# main.net
KiCad netlist of a schematic drawn in Altium Designer
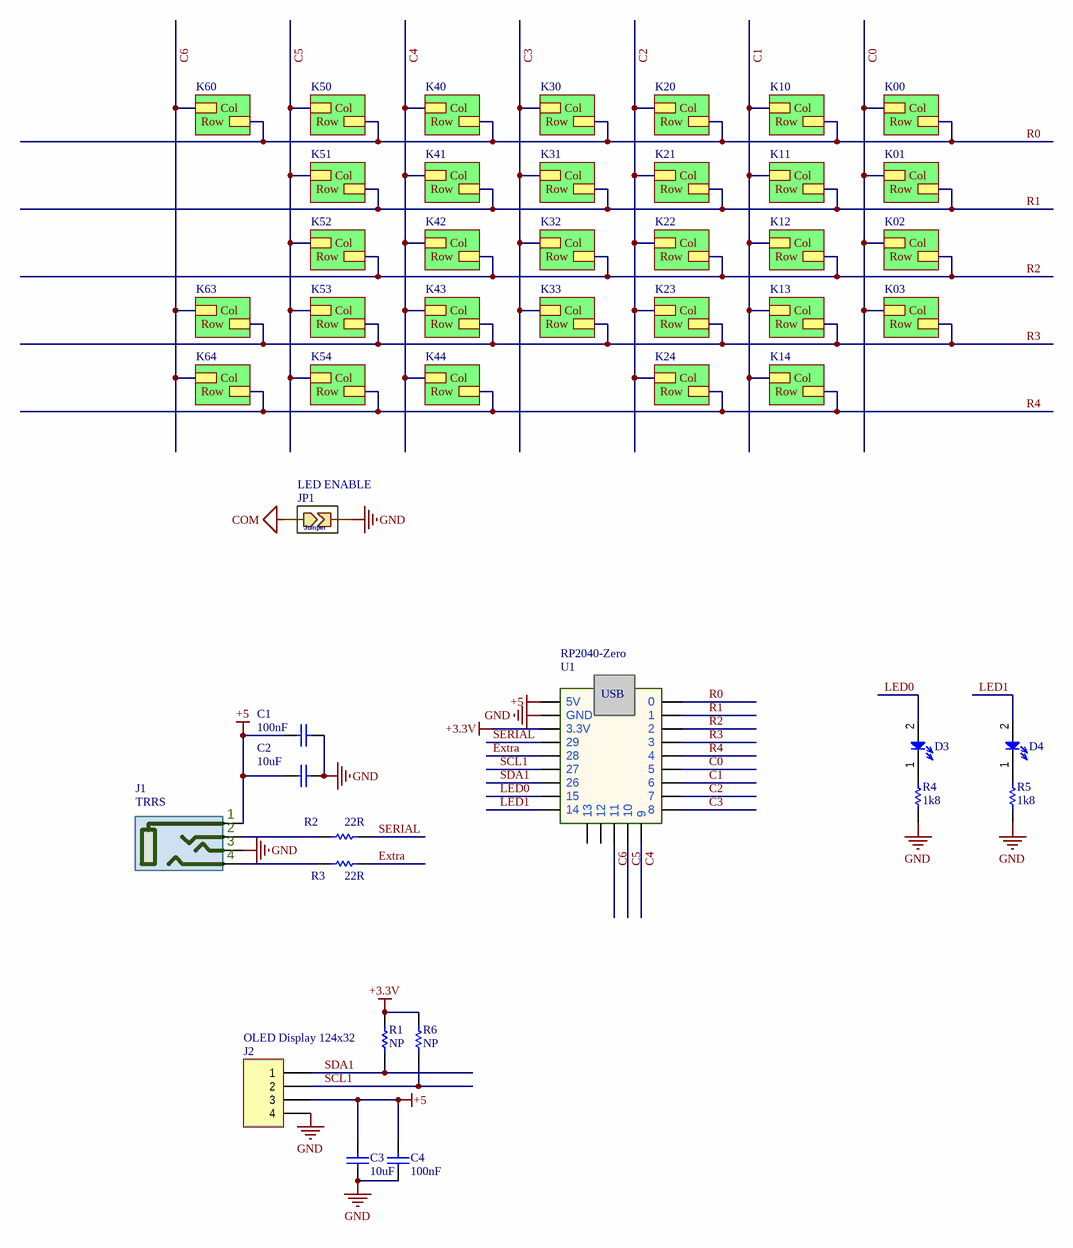
[diagram p0: main.SchDoc]

(export (version "E")
  (design (tool "Eeschema 10.0.6"))
  (components
    (comp (ref "C1")
      (value "100nF")
      (footprint "0402_[1005]")
      (description "Capacitor")
      (libsource (lib "develer_generic") (part "Cap"))
    )
    (comp (ref "C2")
      (value "10uF")
      (footprint "0603_[1608]")
      (description "Capacitor")
      (libsource (lib "develer_generic") (part "Cap"))
    )
    (comp (ref "C3")
      (value "10uF")
      (footprint "0603_[1608]")
      (description "Capacitor")
      (libsource (lib "develer_generic") (part "Cap"))
    )
    (comp (ref "C4")
      (value "100nF")
      (footprint "0402_[1005]")
      (description "Capacitor")
      (libsource (lib "develer_generic") (part "Cap"))
    )
    (comp (ref "D3")
      (value "K")
      (footprint "0402_[1005]_K1-A2_LED")
      (description "Diode Led")
      (fields (field (name "PUBLISHER") "Develer srl"))
      (libsource (lib "develer_generic") (part "DiodeLedSmall"))
    )
    (comp (ref "D4")
      (value "K")
      (footprint "0402_[1005]_K1-A2_LED")
      (description "Diode Led")
      (fields (field (name "PUBLISHER") "Develer srl"))
      (libsource (lib "develer_generic") (part "DiodeLedSmall"))
    )
    (comp (ref "J1")
      (value "TRRS")
      (footprint "CON_PHONE_TRRS_3.5MM_THD")
      (description "headphone socket TRRS (Hong Cheng HC-PJ-320A)")
      (fields (field (name "PUBLISHER") "Develer srl"))
      (libsource (lib "develer_connectors") (part "CON_PHONE_JACK_TSSR"))
    )
    (comp (ref "J2")
      (value "OLED Display 124x32")
      (footprint "HEADER_1X4_2.54MM_THD")
      (description "Header, 4-Pin")
      (fields (field (name "PUBLISHER") "Altium Limited"))
      (libsource (lib "Miscellaneous Connectors") (part "Header 4"))
    )
    (comp (ref "JP1")
      (value "LED ENABLE")
      (footprint "0603_[1608]_JUMPER")
      (description "Jumper SMD")
      (fields (field (name "PUBLISHER") "Develer srl"))
      (libsource (lib "develer_generic") (part "JumperSMD"))
    )
    (comp (ref "R1")
      (value "NP")
      (footprint "0402_[1005]")
      (description "Resistor")
      (fields (field (name "PUBLISHER") "Develer srl"))
      (libsource (lib "develer_generic") (part "Res"))
    )
    (comp (ref "R2")
      (value "22R")
      (footprint "0402_[1005]")
      (description "Resistor")
      (fields (field (name "PUBLISHER") "Develer srl"))
      (libsource (lib "develer_generic") (part "Res"))
    )
    (comp (ref "R3")
      (value "22R")
      (footprint "0402_[1005]")
      (description "Resistor")
      (fields (field (name "PUBLISHER") "Develer srl"))
      (libsource (lib "develer_generic") (part "Res"))
    )
    (comp (ref "R4")
      (value "1k8")
      (footprint "0402_[1005]")
      (description "Resistor")
      (fields (field (name "PUBLISHER") "Develer srl"))
      (libsource (lib "develer_generic") (part "Res"))
    )
    (comp (ref "R5")
      (value "1k8")
      (footprint "0402_[1005]")
      (description "Resistor")
      (fields (field (name "PUBLISHER") "Develer srl"))
      (libsource (lib "develer_generic") (part "Res"))
    )
    (comp (ref "R6")
      (value "NP")
      (footprint "0402_[1005]")
      (description "Resistor")
      (fields (field (name "PUBLISHER") "Develer srl"))
      (libsource (lib "develer_generic") (part "Res"))
    )
    (comp (ref "U1")
      (value "RP2040-Zero")
      (footprint "RP2040-Zero")
      (description "module, mini based on RP4020 (RP2350-Zero)")
      (fields (field (name "PUBLISHER") "Develer srl"))
      (libsource (lib "develer_components") (part "RP2040-Zero"))
    )
  )
  (nets
    (net (code "1") (name "+3.3V") (class "Default")
      (node (ref "R1") (pin "2") (pinfunction "2_2") (pintype "passive"))
      (node (ref "R6") (pin "2") (pinfunction "2_2") (pintype "passive"))
      (node (ref "U1") (pin "20") (pinfunction "3.3V_20") (pintype "passive"))
    )
    (net (code "2") (name "+5") (class "Default")
      (node (ref "C1") (pin "2") (pinfunction "2_2") (pintype "passive"))
      (node (ref "C2") (pin "2") (pinfunction "2_2") (pintype "passive"))
      (node (ref "C3") (pin "2") (pinfunction "2_2") (pintype "passive"))
      (node (ref "C4") (pin "2") (pinfunction "2_2") (pintype "passive"))
      (node (ref "J1") (pin "1") (pinfunction "1_1") (pintype "passive"))
      (node (ref "J2") (pin "3") (pinfunction "3_3") (pintype "passive"))
      (node (ref "U1") (pin "22") (pinfunction "5V_22") (pintype "passive"))
    )
    (net (code "3") (name "/C0") (class "Default")
      (node (ref "U1") (pin "5") (pinfunction "5_5") (pintype "passive"))
    )
    (net (code "4") (name "/C1") (class "Default")
      (node (ref "U1") (pin "6") (pinfunction "6_6") (pintype "passive"))
    )
    (net (code "5") (name "/C2") (class "Default")
      (node (ref "U1") (pin "7") (pinfunction "7_7") (pintype "passive"))
    )
    (net (code "6") (name "/C3") (class "Default")
      (node (ref "U1") (pin "8") (pinfunction "8_8") (pintype "passive"))
    )
    (net (code "7") (name "/C4") (class "Default")
      (node (ref "U1") (pin "9") (pinfunction "9_9") (pintype "passive"))
    )
    (net (code "8") (name "/C5") (class "Default")
      (node (ref "U1") (pin "10") (pinfunction "10_10") (pintype "passive"))
    )
    (net (code "9") (name "/C6") (class "Default")
      (node (ref "U1") (pin "11") (pinfunction "11_11") (pintype "passive"))
    )
    (net (code "10") (name "/Extra") (class "Default")
      (node (ref "R3") (pin "1") (pinfunction "1_1") (pintype "passive"))
      (node (ref "U1") (pin "18") (pinfunction "28_18") (pintype "passive"))
    )
    (net (code "11") (name "/LED0") (class "Default")
      (node (ref "D3") (pin "2") (pinfunction "A_2") (pintype "passive"))
      (node (ref "U1") (pin "15") (pinfunction "15_15") (pintype "passive"))
    )
    (net (code "12") (name "/LED1") (class "Default")
      (node (ref "D4") (pin "2") (pinfunction "A_2") (pintype "passive"))
      (node (ref "U1") (pin "14") (pinfunction "14_14") (pintype "passive"))
    )
    (net (code "13") (name "/R0") (class "Default")
      (node (ref "U1") (pin "0") (pinfunction "0_0") (pintype "passive"))
    )
    (net (code "14") (name "/R1") (class "Default")
      (node (ref "U1") (pin "1") (pinfunction "1_1") (pintype "passive"))
    )
    (net (code "15") (name "/R2") (class "Default")
      (node (ref "U1") (pin "2") (pinfunction "2_2") (pintype "passive"))
    )
    (net (code "16") (name "/R3") (class "Default")
      (node (ref "U1") (pin "3") (pinfunction "3_3") (pintype "passive"))
    )
    (net (code "17") (name "/R4") (class "Default")
      (node (ref "U1") (pin "4") (pinfunction "4_4") (pintype "passive"))
    )
    (net (code "18") (name "/SCL1") (class "Default")
      (node (ref "J2") (pin "2") (pinfunction "2_2") (pintype "passive"))
      (node (ref "R6") (pin "1") (pinfunction "1_1") (pintype "passive"))
      (node (ref "U1") (pin "17") (pinfunction "27_17") (pintype "passive"))
    )
    (net (code "19") (name "/SDA1") (class "Default")
      (node (ref "J2") (pin "1") (pinfunction "1_1") (pintype "passive"))
      (node (ref "R1") (pin "1") (pinfunction "1_1") (pintype "passive"))
      (node (ref "U1") (pin "16") (pinfunction "26_16") (pintype "passive"))
    )
    (net (code "20") (name "/SERIAL") (class "Default")
      (node (ref "R2") (pin "1") (pinfunction "1_1") (pintype "passive"))
      (node (ref "U1") (pin "19") (pinfunction "29_19") (pintype "passive"))
    )
    (net (code "21") (name "COM") (class "Default")
      (node (ref "JP1") (pin "1") (pinfunction "1_1") (pintype "passive"))
    )
    (net (code "22") (name "GND") (class "Default")
      (node (ref "C1") (pin "1") (pinfunction "1_1") (pintype "passive"))
      (node (ref "C2") (pin "1") (pinfunction "1_1") (pintype "passive"))
      (node (ref "C3") (pin "1") (pinfunction "1_1") (pintype "passive"))
      (node (ref "C4") (pin "1") (pinfunction "1_1") (pintype "passive"))
      (node (ref "J1") (pin "3") (pinfunction "3_3") (pintype "passive"))
      (node (ref "J2") (pin "4") (pinfunction "4_4") (pintype "passive"))
      (node (ref "JP1") (pin "2") (pinfunction "2_2") (pintype "passive"))
      (node (ref "R4") (pin "1") (pinfunction "1_1") (pintype "passive"))
      (node (ref "R5") (pin "1") (pinfunction "1_1") (pintype "passive"))
      (node (ref "U1") (pin "21") (pinfunction "GND_21") (pintype "passive"))
    )
    (net (code "23") (name "Net-(D3-K)") (class "Default")
      (node (ref "D3") (pin "1") (pinfunction "K_1") (pintype "passive"))
      (node (ref "R4") (pin "2") (pinfunction "2_2") (pintype "passive"))
    )
    (net (code "24") (name "Net-(D4-K)") (class "Default")
      (node (ref "D4") (pin "1") (pinfunction "K_1") (pintype "passive"))
      (node (ref "R5") (pin "2") (pinfunction "2_2") (pintype "passive"))
    )
    (net (code "25") (name "Net-(J1-Pad2)") (class "Default")
      (node (ref "J1") (pin "2") (pinfunction "2_2") (pintype "passive"))
      (node (ref "R2") (pin "2") (pinfunction "2_2") (pintype "passive"))
    )
    (net (code "26") (name "Net-(J1-Pad4)") (class "Default")
      (node (ref "J1") (pin "4") (pinfunction "4_4") (pintype "passive"))
      (node (ref "R3") (pin "2") (pinfunction "2_2") (pintype "passive"))
    )
    (net (code "27") (name "unconnected-(U1-Pad12)") (class "Default")
      (node (ref "U1") (pin "12") (pinfunction "12_12") (pintype "passive"))
    )
    (net (code "28") (name "unconnected-(U1-Pad13)") (class "Default")
      (node (ref "U1") (pin "13") (pinfunction "13_13") (pintype "passive"))
    )
  )
)
